# EV_Schematics.net
KiCad netlist of a schematic drawn in Altium Designer
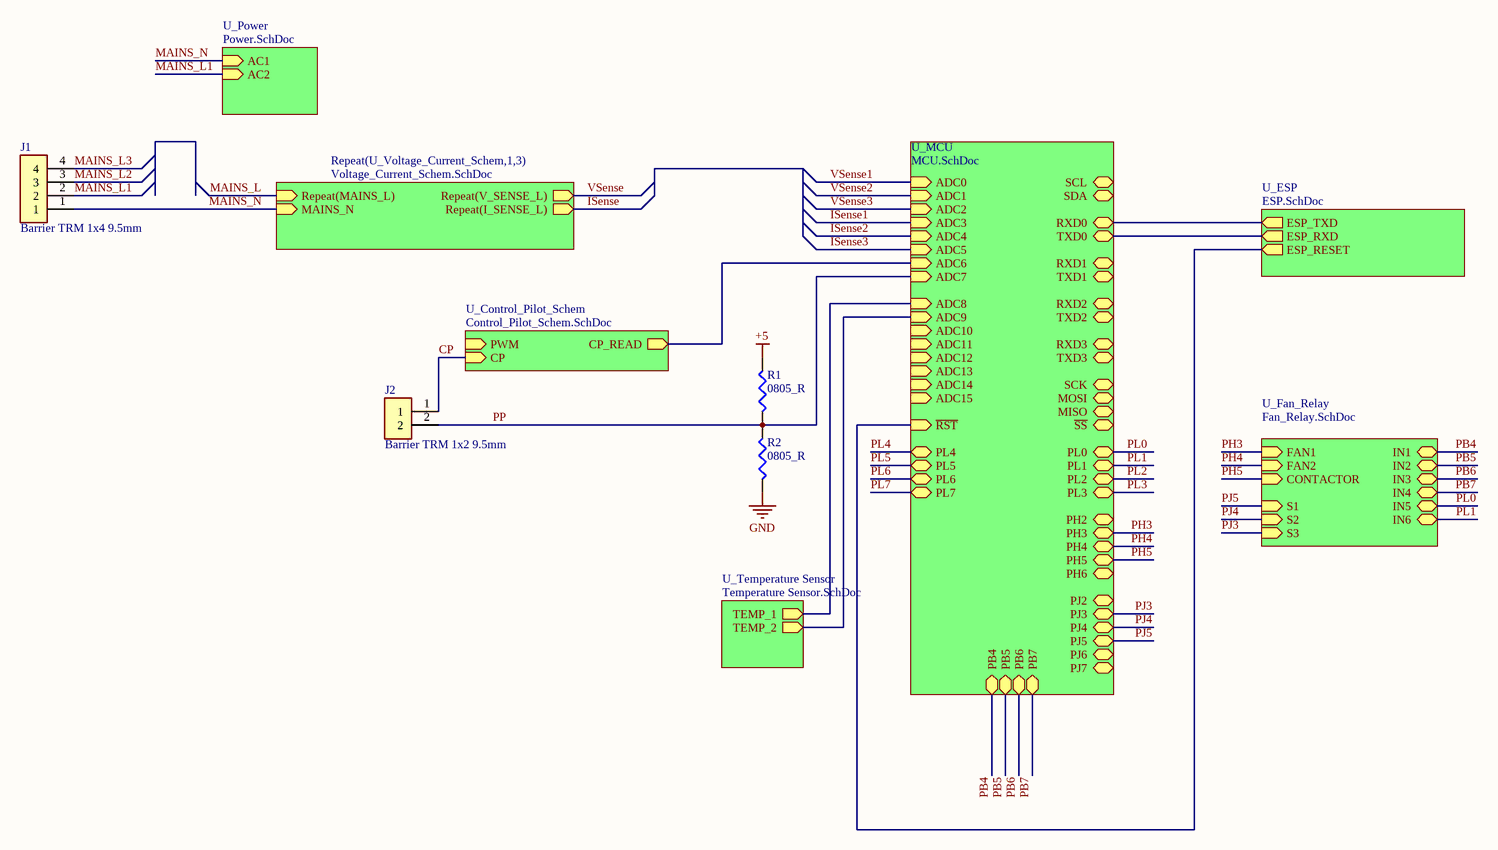
[diagram p0: EV_Schematics.SchDoc]

(export (version "E")
  (design (tool "Eeschema 10.0.6"))
  (components
    (comp (ref "J1")
      (value "Barrier TRM 1x4 9.5mm")
      (footprint "BARRIER_4_9.5mm")
      (description "CONN BARRIER STRIP 4CIRC 0.374\"")
      (libsource (lib "CAD_Symbols") (part "Barrier BLK_4"))
    )
    (comp (ref "J2")
      (value "Barrier TRM 1x2 9.5mm")
      (footprint "BARRIER_9.5MM")
      (description "CONN BARRIER STRIP 2CIRC 0.374\"")
      (libsource (lib "CAD_Symbols") (part "Barrier BLK"))
    )
    (comp (ref "R1")
      (value "0805_R")
      (footprint "R0805")
      (libsource (lib "TimerSMD_Components") (part "0805 Resistor"))
    )
    (comp (ref "R2")
      (value "0805_R")
      (footprint "R0805")
      (libsource (lib "TimerSMD_Components") (part "0805 Resistor"))
    )
  )
  (nets
    (net (code "1") (name "+5") (class "Default")
      (node (ref "R1") (pin "2") (pinfunction "2_2") (pintype "passive"))
    )
    (net (code "8") (name "/CP") (class "Default")
      (node (ref "J2") (pin "1") (pinfunction "1_1") (pintype "passive"))
    )
    (net (code "18") (name "/MAINS_L1") (class "Default")
      (node (ref "J1") (pin "2") (pinfunction "2_2") (pintype "passive"))
    )
    (net (code "19") (name "/MAINS_L2") (class "Default")
      (node (ref "J1") (pin "3") (pinfunction "3_3") (pintype "passive"))
    )
    (net (code "20") (name "/MAINS_L3") (class "Default")
      (node (ref "J1") (pin "4") (pinfunction "4_4") (pintype "passive"))
    )
    (net (code "21") (name "/MAINS_N") (class "Default")
      (node (ref "J1") (pin "1") (pinfunction "1_1") (pintype "passive"))
    )
    (net (code "47") (name "/PP") (class "Default")
      (node (ref "J2") (pin "2") (pinfunction "2_2") (pintype "passive"))
      (node (ref "R1") (pin "1") (pinfunction "1_1") (pintype "passive"))
      (node (ref "R2") (pin "2") (pinfunction "2_2") (pintype "passive"))
    )
    (net (code "65") (name "GND") (class "Default")
      (node (ref "R2") (pin "1") (pinfunction "1_1") (pintype "passive"))
    )
  )
)
